# LTC6820_Test_Board.net
KiCad netlist of a schematic drawn in EAGLE
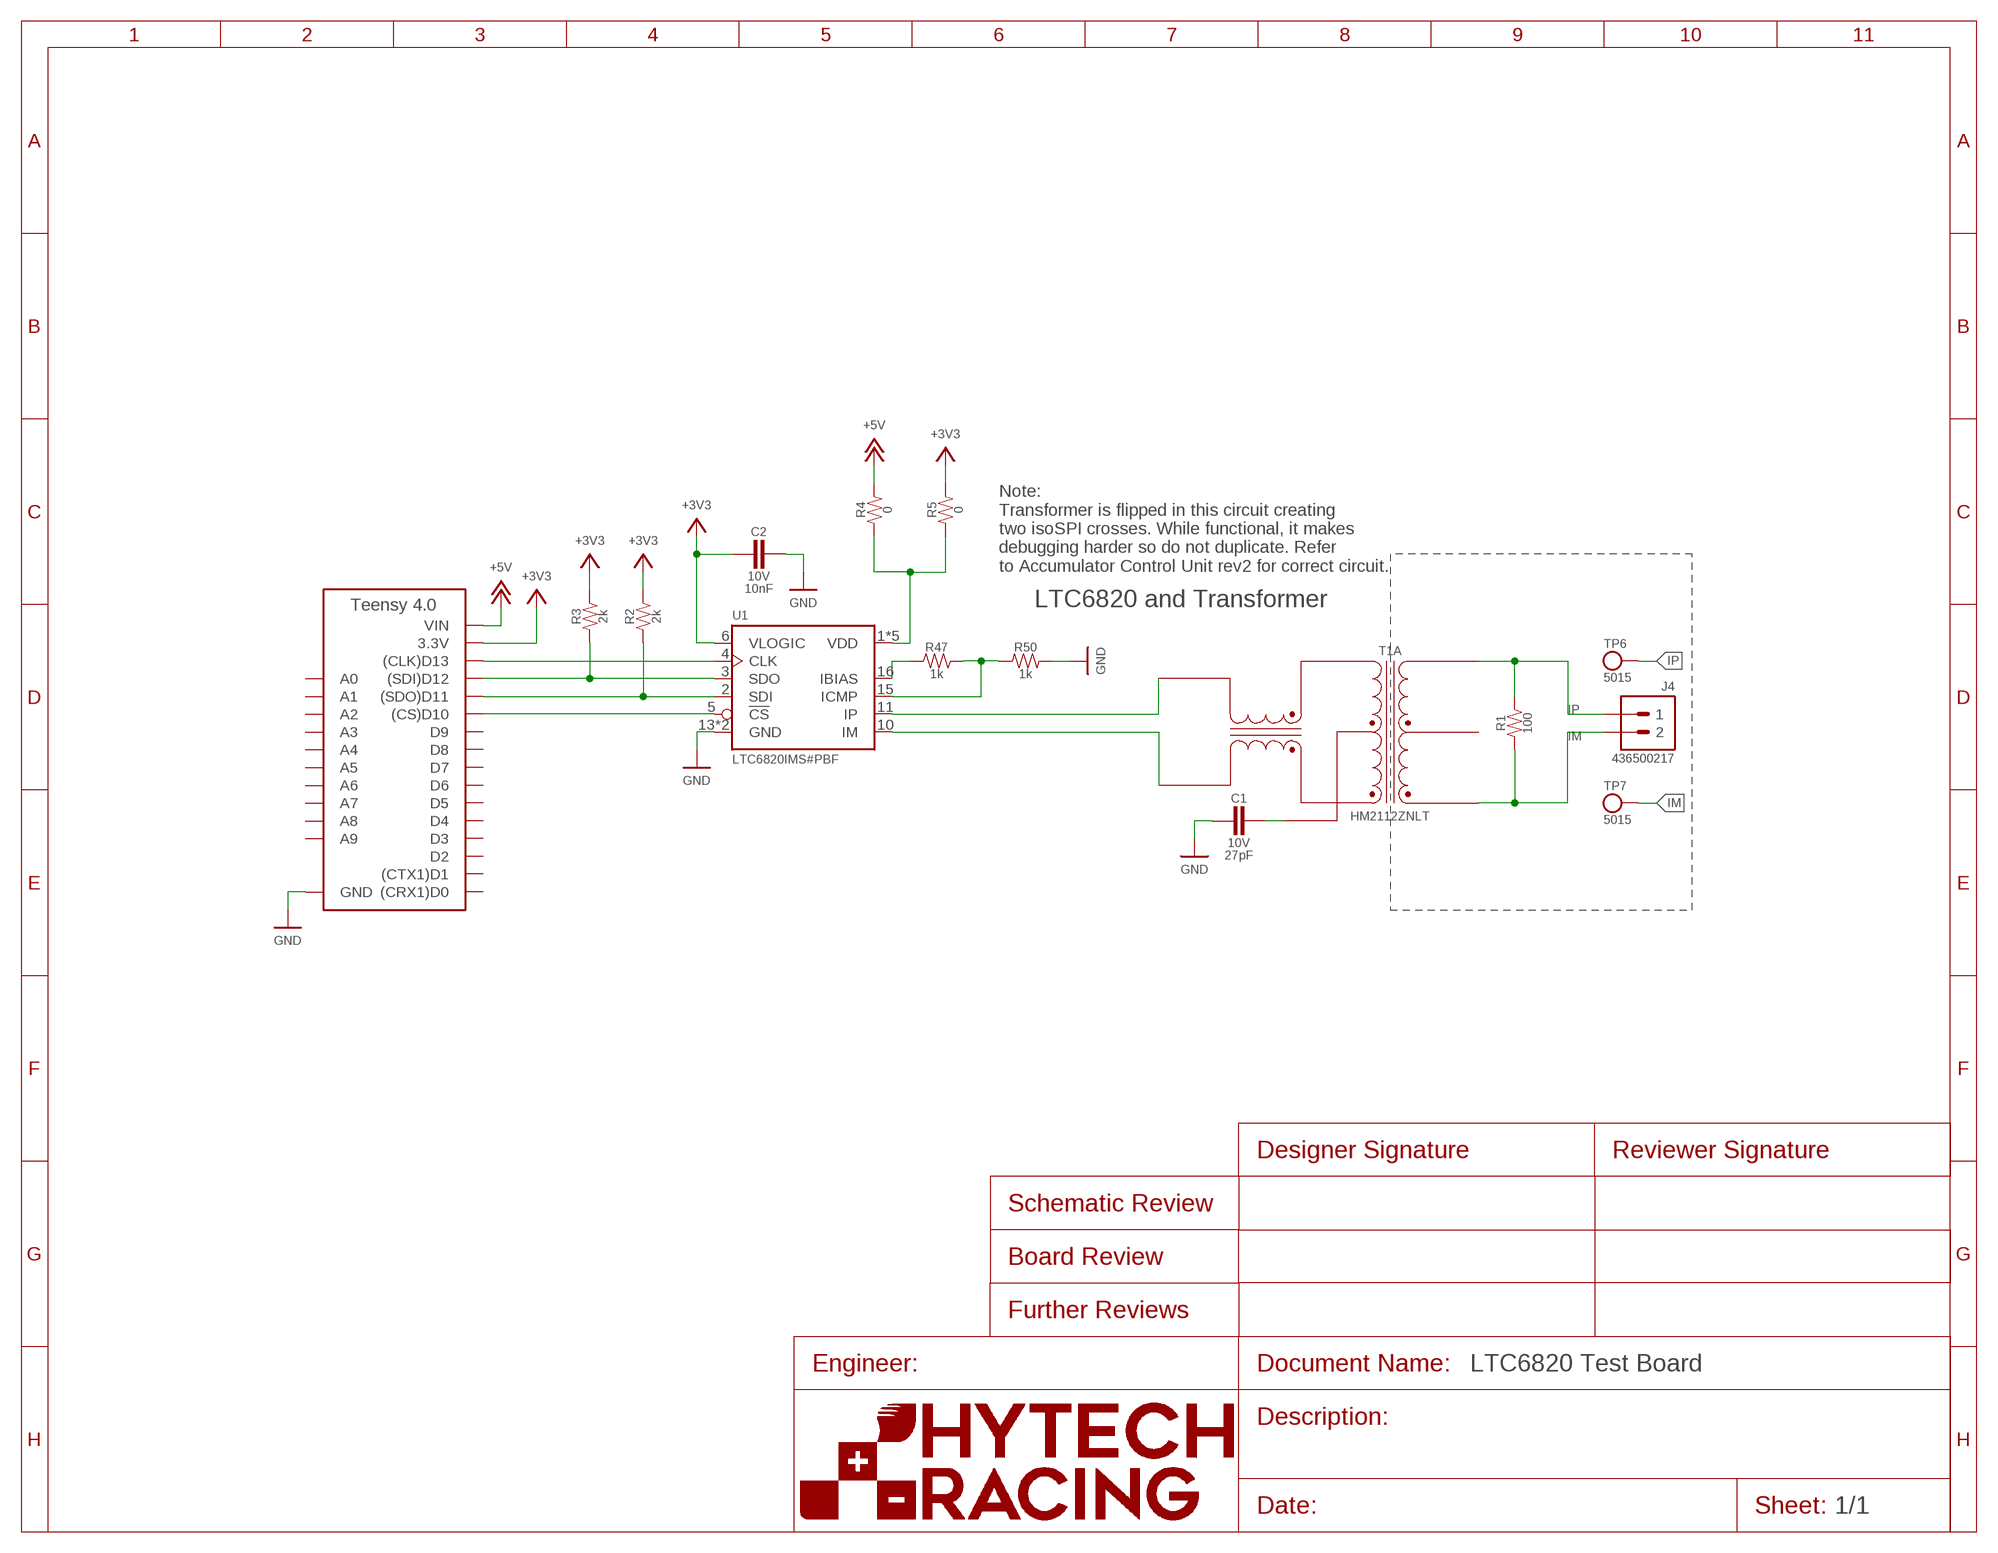
[diagram p0: schematic, sheet 1]

(export (version "E")
  (design (tool "Eeschema 10.0.6"))
  (components
    (comp (ref "A1")
      (value "TEENSY_4.0")
      (footprint "eagle-import:TEENSY_SHORT")
      (libsource (lib "eagle-import") (part "TEENSY_4.0"))
    )
    (comp (ref "C1")
      (value "CAPACITOR_0603_10V_27PF")
      (footprint "eagle-import:0603-CAP")
      (fields
        (field (name "CAPACITANCE") "27pF")
        (field (name "MANUFACTURER") "Vishay Vitramon")
        (field (name "MPN") "77-VJ0603A270FXQCBC")
        (field (name "TOLERANCE") "1%")
        (field (name "VOLTAGE") "10V")
      )
      (libsource (lib "eagle-import") (part "CAPACITOR_?_060310V_27PF"))
    )
    (comp (ref "C2")
      (value "CAPACITOR_0603_10V_10NF")
      (footprint "eagle-import:0603-CAP")
      (fields
        (field (name "CAPACITANCE") "10nF")
        (field (name "MANUFACTURER") "Yageo")
        (field (name "MPN") "CC0603KRX7R6BB103")
        (field (name "TOLERANCE") "10%")
        (field (name "VOLTAGE") "10V")
      )
      (libsource (lib "eagle-import") (part "CAPACITOR_?_060310V_10NF"))
    )
    (comp (ref "J4")
      (value "CONNECTOR-2_MF_T_V_")
      (footprint "eagle-import:MOLEX_MICROFIT_PTH_VERTICAL_02_SINGLE")
      (fields (field (name "MPN") "436500217") (field (name "MANUFACTURER") "MOLEX"))
      (libsource (lib "eagle-import") (part "CONNECTOR-2_?_MF_T_V"))
    )
    (comp (ref "R1")
      (value "RESISTOR_0603_100")
      (footprint "eagle-import:0603-RES")
      (fields
        (field (name "MANUFACTURER") "Yageo")
        (field (name "MPN") "RC0603FR-07100RL")
        (field (name "POWER") "0.1W")
        (field (name "RESISTANCE") "100")
      )
      (libsource (lib "eagle-import") (part "RESISTOR_?_0603100"))
    )
    (comp (ref "R2")
      (value "RESISTOR_0603_2K")
      (footprint "eagle-import:0603-RES")
      (fields
        (field (name "MANUFACTURER") "Panasonic Electronic Components")
        (field (name "MPN") "ERA-3ARB202V")
        (field (name "POWER") "0.1W")
        (field (name "RESISTANCE") "2k")
      )
      (libsource (lib "eagle-import") (part "RESISTOR_?_06032K"))
    )
    (comp (ref "R3")
      (value "RESISTOR_0603_2K")
      (footprint "eagle-import:0603-RES")
      (fields
        (field (name "MANUFACTURER") "Panasonic Electronic Components")
        (field (name "MPN") "ERA-3ARB202V")
        (field (name "POWER") "0.1W")
        (field (name "RESISTANCE") "2k")
      )
      (libsource (lib "eagle-import") (part "RESISTOR_?_06032K"))
    )
    (comp (ref "R4")
      (value "RESISTOR_0603_0")
      (footprint "eagle-import:0603-RES")
      (fields
        (field (name "MANUFACTURER") "Yageo")
        (field (name "MPN") "RC0603FR-070RL")
        (field (name "POWER") "0.1W")
        (field (name "RESISTANCE") "0")
      )
      (libsource (lib "eagle-import") (part "RESISTOR_?_06030"))
    )
    (comp (ref "R5")
      (value "RESISTOR_0603_0")
      (footprint "eagle-import:0603-RES")
      (fields
        (field (name "MANUFACTURER") "Yageo")
        (field (name "MPN") "RC0603FR-070RL")
        (field (name "POWER") "0.1W")
        (field (name "RESISTANCE") "0")
      )
      (libsource (lib "eagle-import") (part "RESISTOR_?_06030"))
    )
    (comp (ref "R47")
      (value "RESISTOR_0603_1K")
      (footprint "eagle-import:0603-RES")
      (fields
        (field (name "MANUFACTURER") "Yageo")
        (field (name "MPN") "RC0603FR-071KL")
        (field (name "POWER") "0.1W")
        (field (name "RESISTANCE") "1k")
      )
      (libsource (lib "eagle-import") (part "RESISTOR_?_06031K"))
    )
    (comp (ref "R50")
      (value "RESISTOR_0603_1K")
      (footprint "eagle-import:0603-RES")
      (fields
        (field (name "MANUFACTURER") "Yageo")
        (field (name "MPN") "RC0603FR-071KL")
        (field (name "POWER") "0.1W")
        (field (name "RESISTANCE") "1k")
      )
      (libsource (lib "eagle-import") (part "RESISTOR_?_06031K"))
    )
    (comp (ref "T1")
      (value "TRANSFORMER_HM2112ZNLT_AIRGAP")
      (footprint "eagle-import:HM2112ZNLT_AIRGAP")
      (fields (field (name "MPN") "HM2112ZNLT") (field (name "MANUFACTURER") "Pulse Electronics"))
      (libsource (lib "eagle-import") (part "TRANSFORMER_HM2112ZNLT_AIRGAP"))
    )
    (comp (ref "TP6")
      (value "TEST_POINT")
      (footprint "eagle-import:MICRO_MINIATURE")
      (fields (field (name "MPN") "5015") (field (name "MANUFACTURER") "Keystone Electronics"))
      (libsource (lib "eagle-import") (part "TEST_POINT"))
    )
    (comp (ref "TP7")
      (value "TEST_POINT")
      (footprint "eagle-import:MICRO_MINIATURE")
      (fields (field (name "MPN") "5015") (field (name "MANUFACTURER") "Keystone Electronics"))
      (libsource (lib "eagle-import") (part "TEST_POINT"))
    )
    (comp (ref "U1")
      (value "LTC6820")
      (footprint "eagle-import:MSOP-16")
      (fields (field (name "MPN") "LTC6820IMS#PBF") (field (name "MANUFACTURER") "Analog Devices"))
      (libsource (lib "eagle-import") (part "LTC6820"))
    )
  )
  (nets
    (net (code "1") (name "+3V3") (class "Default")
      (node (ref "A1") (pin "3.3V") (pinfunction "3.3V_3.3V") (pintype "power_in"))
      (node (ref "C2") (pin "2") (pinfunction "2_2") (pintype "passive"))
      (node (ref "R2") (pin "2") (pinfunction "2_2") (pintype "passive"))
      (node (ref "R3") (pin "2") (pinfunction "2_2") (pintype "passive"))
      (node (ref "R5") (pin "2") (pinfunction "2_2") (pintype "passive"))
      (node (ref "U1") (pin "6") (pinfunction "VLOGIC_6") (pintype "bidirectional"))
    )
    (net (code "2") (name "+5V") (class "Default")
      (node (ref "A1") (pin "VIN") (pinfunction "VIN_VIN") (pintype "power_in"))
      (node (ref "R4") (pin "2") (pinfunction "2_2") (pintype "passive"))
    )
    (net (code "3") (name "GND") (class "Default")
      (node (ref "A1") (pin "AGND/GND") (pinfunction "GND_AGND/GND") (pintype "power_in"))
      (node (ref "A1") (pin "GND") (pinfunction "GND_GND") (pintype "power_in"))
      (node (ref "C1") (pin "2") (pinfunction "2_2") (pintype "passive"))
      (node (ref "C2") (pin "1") (pinfunction "1_1") (pintype "passive"))
      (node (ref "R50") (pin "2") (pinfunction "2_2") (pintype "passive"))
      (node (ref "U1") (pin "13") (pinfunction "GND_13") (pintype "power_in"))
      (node (ref "U1") (pin "14") (pinfunction "GND_14") (pintype "power_in"))
    )
    (net (code "4") (name "IM") (class "Default")
      (node (ref "J4") (pin "2") (pinfunction "2_2") (pintype "passive"))
      (node (ref "R1") (pin "1") (pinfunction "1_1") (pintype "passive"))
      (node (ref "T1") (pin "1") (pinfunction "MX+_1") (pintype "passive"))
      (node (ref "TP7") (pin "1") (pinfunction "P$1_1") (pintype "passive"))
    )
    (net (code "5") (name "IP") (class "Default")
      (node (ref "J4") (pin "1") (pinfunction "1_1") (pintype "passive"))
      (node (ref "R1") (pin "2") (pinfunction "2_2") (pintype "passive"))
      (node (ref "T1") (pin "3") (pinfunction "MX-_3") (pintype "passive"))
      (node (ref "TP6") (pin "1") (pinfunction "P$1_1") (pintype "passive"))
    )
    (net (code "6") (name "Net-(A1-(CLK)D13)") (class "Default")
      (node (ref "A1") (pin "D13") (pinfunction "(CLK)D13_D13") (pintype "bidirectional"))
      (node (ref "U1") (pin "4") (pinfunction "CLK_4") (pintype "input"))
    )
    (net (code "7") (name "Net-(A1-(CS)D10)") (class "Default")
      (node (ref "A1") (pin "D10") (pinfunction "(CS)D10_D10") (pintype "bidirectional"))
      (node (ref "U1") (pin "5") (pinfunction "~{CS}_5") (pintype "input"))
    )
    (net (code "8") (name "Net-(A1-(SDI)D12)") (class "Default")
      (node (ref "A1") (pin "D12") (pinfunction "(SDI)D12_D12") (pintype "bidirectional"))
      (node (ref "R3") (pin "1") (pinfunction "1_1") (pintype "passive"))
      (node (ref "U1") (pin "3") (pinfunction "SDO_3") (pintype "open_collector"))
    )
    (net (code "9") (name "Net-(A1-(SDO)D11)") (class "Default")
      (node (ref "A1") (pin "D11") (pinfunction "(SDO)D11_D11") (pintype "bidirectional"))
      (node (ref "R2") (pin "1") (pinfunction "1_1") (pintype "passive"))
      (node (ref "U1") (pin "2") (pinfunction "SDI_2") (pintype "open_collector"))
    )
    (net (code "10") (name "Net-(R4-Pad1)") (class "Default")
      (node (ref "R4") (pin "1") (pinfunction "1_1") (pintype "passive"))
      (node (ref "R5") (pin "1") (pinfunction "1_1") (pintype "passive"))
      (node (ref "U1") (pin "1") (pinfunction "VDD_1") (pintype "power_in"))
      (node (ref "U1") (pin "12") (pinfunction "VDD_12") (pintype "power_in"))
      (node (ref "U1") (pin "7") (pinfunction "VDD_7") (pintype "power_in"))
      (node (ref "U1") (pin "8") (pinfunction "VDD_8") (pintype "power_in"))
      (node (ref "U1") (pin "9") (pinfunction "VDD_9") (pintype "power_in"))
    )
    (net (code "11") (name "Net-(T1A-TCT)") (class "Default")
      (node (ref "C1") (pin "1") (pinfunction "1_1") (pintype "passive"))
      (node (ref "T1") (pin "11") (pinfunction "TCT_11") (pintype "passive"))
    )
    (net (code "12") (name "Net-(T1A-TD+)") (class "Default")
      (node (ref "T1") (pin "12") (pinfunction "TD+_12") (pintype "passive"))
      (node (ref "U1") (pin "10") (pinfunction "IM_10") (pintype "bidirectional"))
    )
    (net (code "13") (name "Net-(T1A-TD-)") (class "Default")
      (node (ref "T1") (pin "10") (pinfunction "TD-_10") (pintype "passive"))
      (node (ref "U1") (pin "11") (pinfunction "IP_11") (pintype "bidirectional"))
    )
    (net (code "14") (name "Net-(U1-IBIAS)") (class "Default")
      (node (ref "R47") (pin "1") (pinfunction "1_1") (pintype "passive"))
      (node (ref "U1") (pin "16") (pinfunction "IBIAS_16") (pintype "bidirectional"))
    )
    (net (code "15") (name "Net-(U1-ICMP)") (class "Default")
      (node (ref "R47") (pin "2") (pinfunction "2_2") (pintype "passive"))
      (node (ref "R50") (pin "1") (pinfunction "1_1") (pintype "passive"))
      (node (ref "U1") (pin "15") (pinfunction "ICMP_15") (pintype "bidirectional"))
    )
    (net (code "16") (name "unconnected-(A1-(CRX1)D0-PadD0)") (class "Default")
      (node (ref "A1") (pin "D0") (pinfunction "(CRX1)D0_D0") (pintype "bidirectional"))
    )
    (net (code "17") (name "unconnected-(A1-(CTX1)D1-PadD1)") (class "Default")
      (node (ref "A1") (pin "D1") (pinfunction "(CTX1)D1_D1") (pintype "bidirectional"))
    )
    (net (code "18") (name "unconnected-(A1-A0-PadD14)") (class "Default")
      (node (ref "A1") (pin "D14") (pinfunction "A0_D14") (pintype "bidirectional"))
    )
    (net (code "19") (name "unconnected-(A1-A1-PadD15)") (class "Default")
      (node (ref "A1") (pin "D15") (pinfunction "A1_D15") (pintype "bidirectional"))
    )
    (net (code "20") (name "unconnected-(A1-A2-PadD16)") (class "Default")
      (node (ref "A1") (pin "D16") (pinfunction "A2_D16") (pintype "bidirectional"))
    )
    (net (code "21") (name "unconnected-(A1-A3-PadD17)") (class "Default")
      (node (ref "A1") (pin "D17") (pinfunction "A3_D17") (pintype "bidirectional"))
    )
    (net (code "22") (name "unconnected-(A1-A4-PadD18)") (class "Default")
      (node (ref "A1") (pin "D18") (pinfunction "A4_D18") (pintype "bidirectional"))
    )
    (net (code "23") (name "unconnected-(A1-A5-PadD19)") (class "Default")
      (node (ref "A1") (pin "D19") (pinfunction "A5_D19") (pintype "bidirectional"))
    )
    (net (code "24") (name "unconnected-(A1-A6-PadD20)") (class "Default")
      (node (ref "A1") (pin "D20") (pinfunction "A6_D20") (pintype "bidirectional"))
    )
    (net (code "25") (name "unconnected-(A1-A7-PadD21)") (class "Default")
      (node (ref "A1") (pin "D21") (pinfunction "A7_D21") (pintype "bidirectional"))
    )
    (net (code "26") (name "unconnected-(A1-A8-PadD22)") (class "Default")
      (node (ref "A1") (pin "D22") (pinfunction "A8_D22") (pintype "bidirectional"))
    )
    (net (code "27") (name "unconnected-(A1-A9-PadD23)") (class "Default")
      (node (ref "A1") (pin "D23") (pinfunction "A9_D23") (pintype "bidirectional"))
    )
    (net (code "28") (name "unconnected-(A1-PadD2)") (class "Default")
      (node (ref "A1") (pin "D2") (pinfunction "D2_D2") (pintype "bidirectional"))
    )
    (net (code "29") (name "unconnected-(A1-PadD3)") (class "Default")
      (node (ref "A1") (pin "D3") (pinfunction "D3_D3") (pintype "bidirectional"))
    )
    (net (code "30") (name "unconnected-(A1-PadD4)") (class "Default")
      (node (ref "A1") (pin "D4") (pinfunction "D4_D4") (pintype "bidirectional"))
    )
    (net (code "31") (name "unconnected-(A1-PadD5)") (class "Default")
      (node (ref "A1") (pin "D5") (pinfunction "D5_D5") (pintype "bidirectional"))
    )
    (net (code "32") (name "unconnected-(A1-PadD6)") (class "Default")
      (node (ref "A1") (pin "D6") (pinfunction "D6_D6") (pintype "bidirectional"))
    )
    (net (code "33") (name "unconnected-(A1-PadD7)") (class "Default")
      (node (ref "A1") (pin "D7") (pinfunction "D7_D7") (pintype "bidirectional"))
    )
    (net (code "34") (name "unconnected-(A1-PadD8)") (class "Default")
      (node (ref "A1") (pin "D8") (pinfunction "D8_D8") (pintype "bidirectional"))
    )
    (net (code "35") (name "unconnected-(A1-PadD9)") (class "Default")
      (node (ref "A1") (pin "D9") (pinfunction "D9_D9") (pintype "bidirectional"))
    )
    (net (code "36") (name "unconnected-(T1A-MCT-Pad2)") (class "Default")
      (node (ref "T1") (pin "2") (pinfunction "MCT_2") (pintype "passive"))
    )
  )
)
